# SmartVision.net
KiCad netlist of a schematic drawn in EAGLE
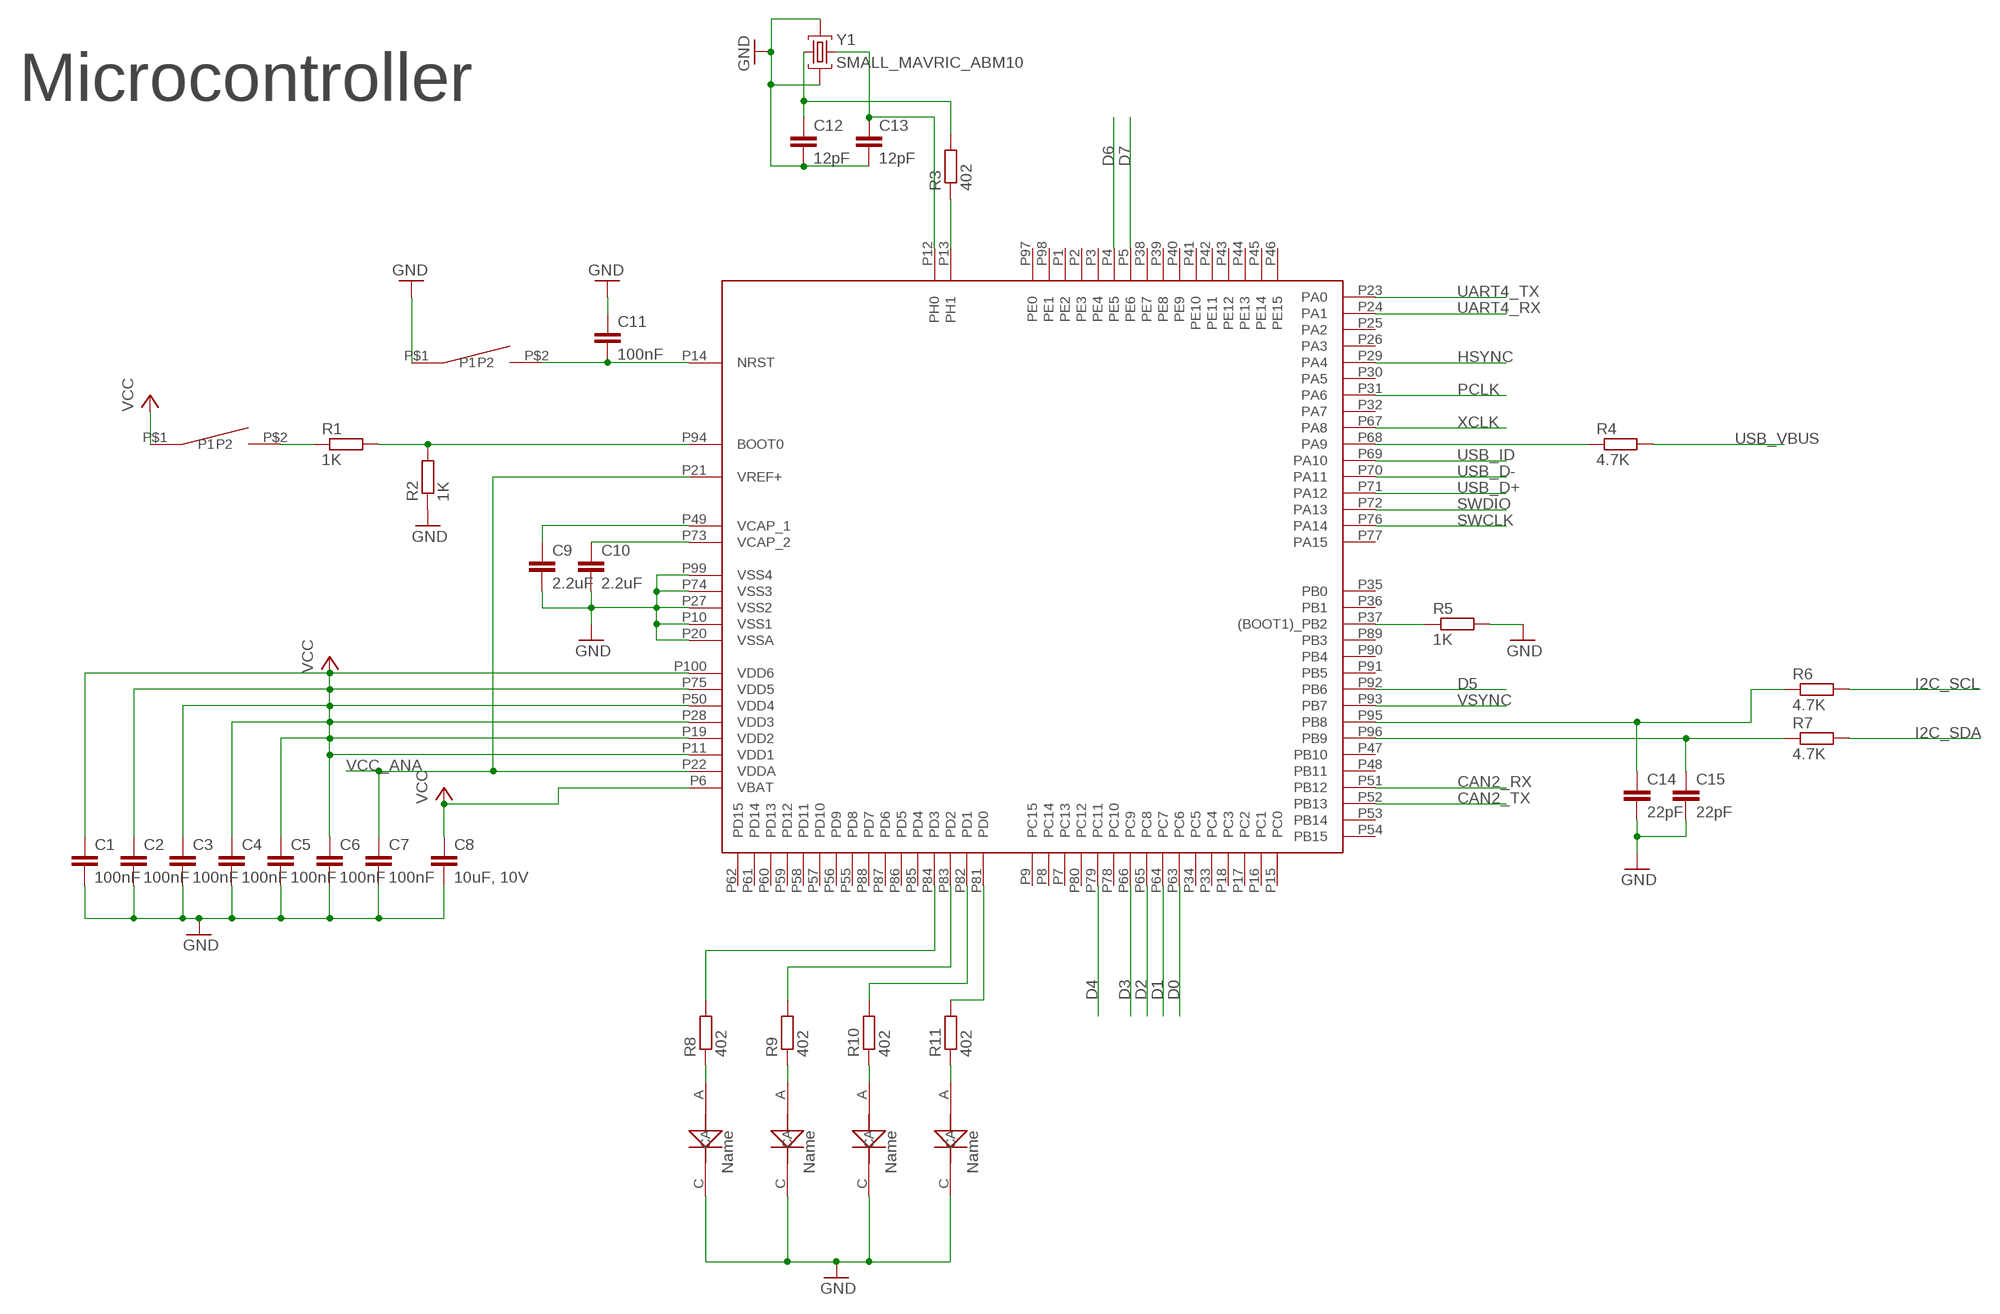
[diagram p0: schematic, sheet 1]
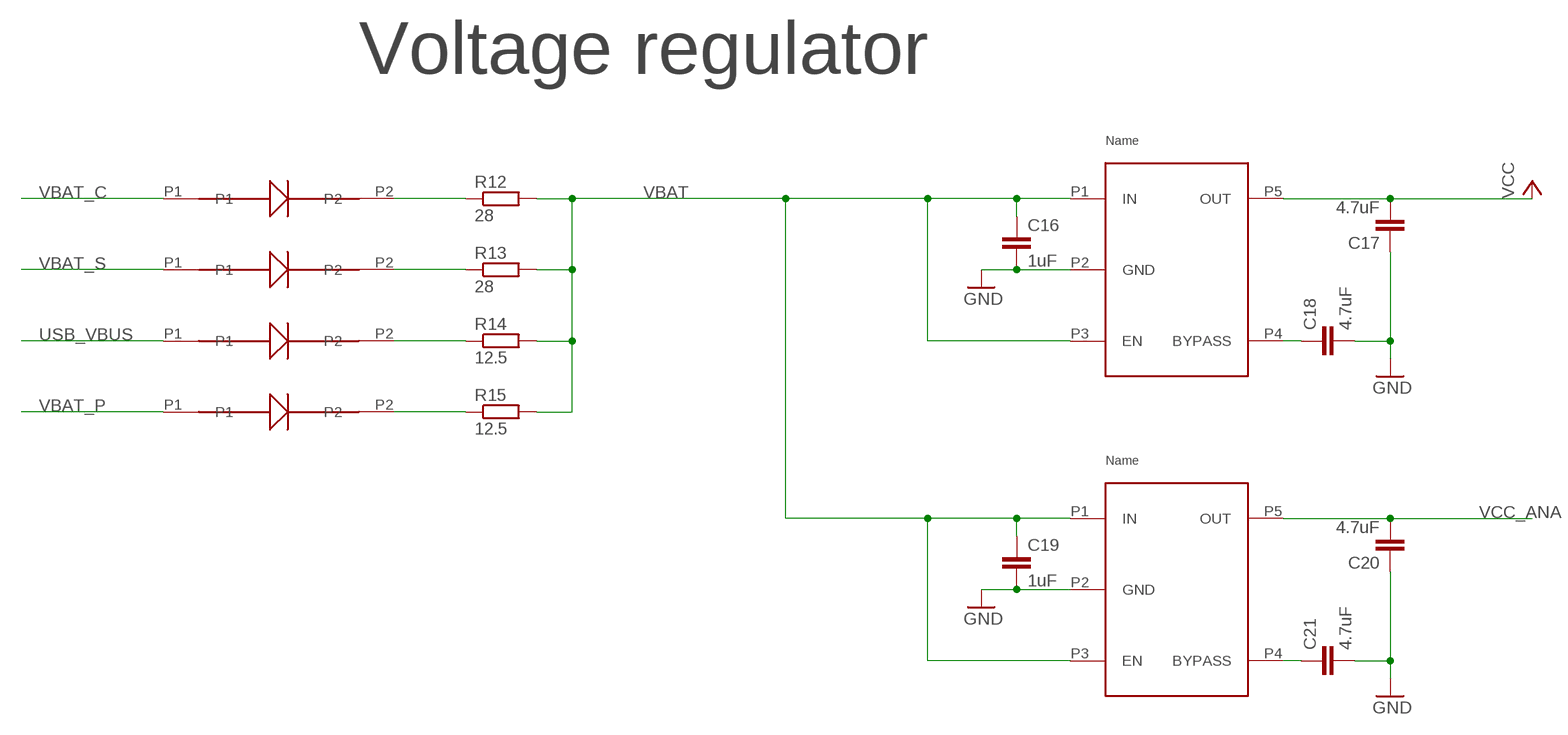
[diagram p1: schematic, sheet 2]
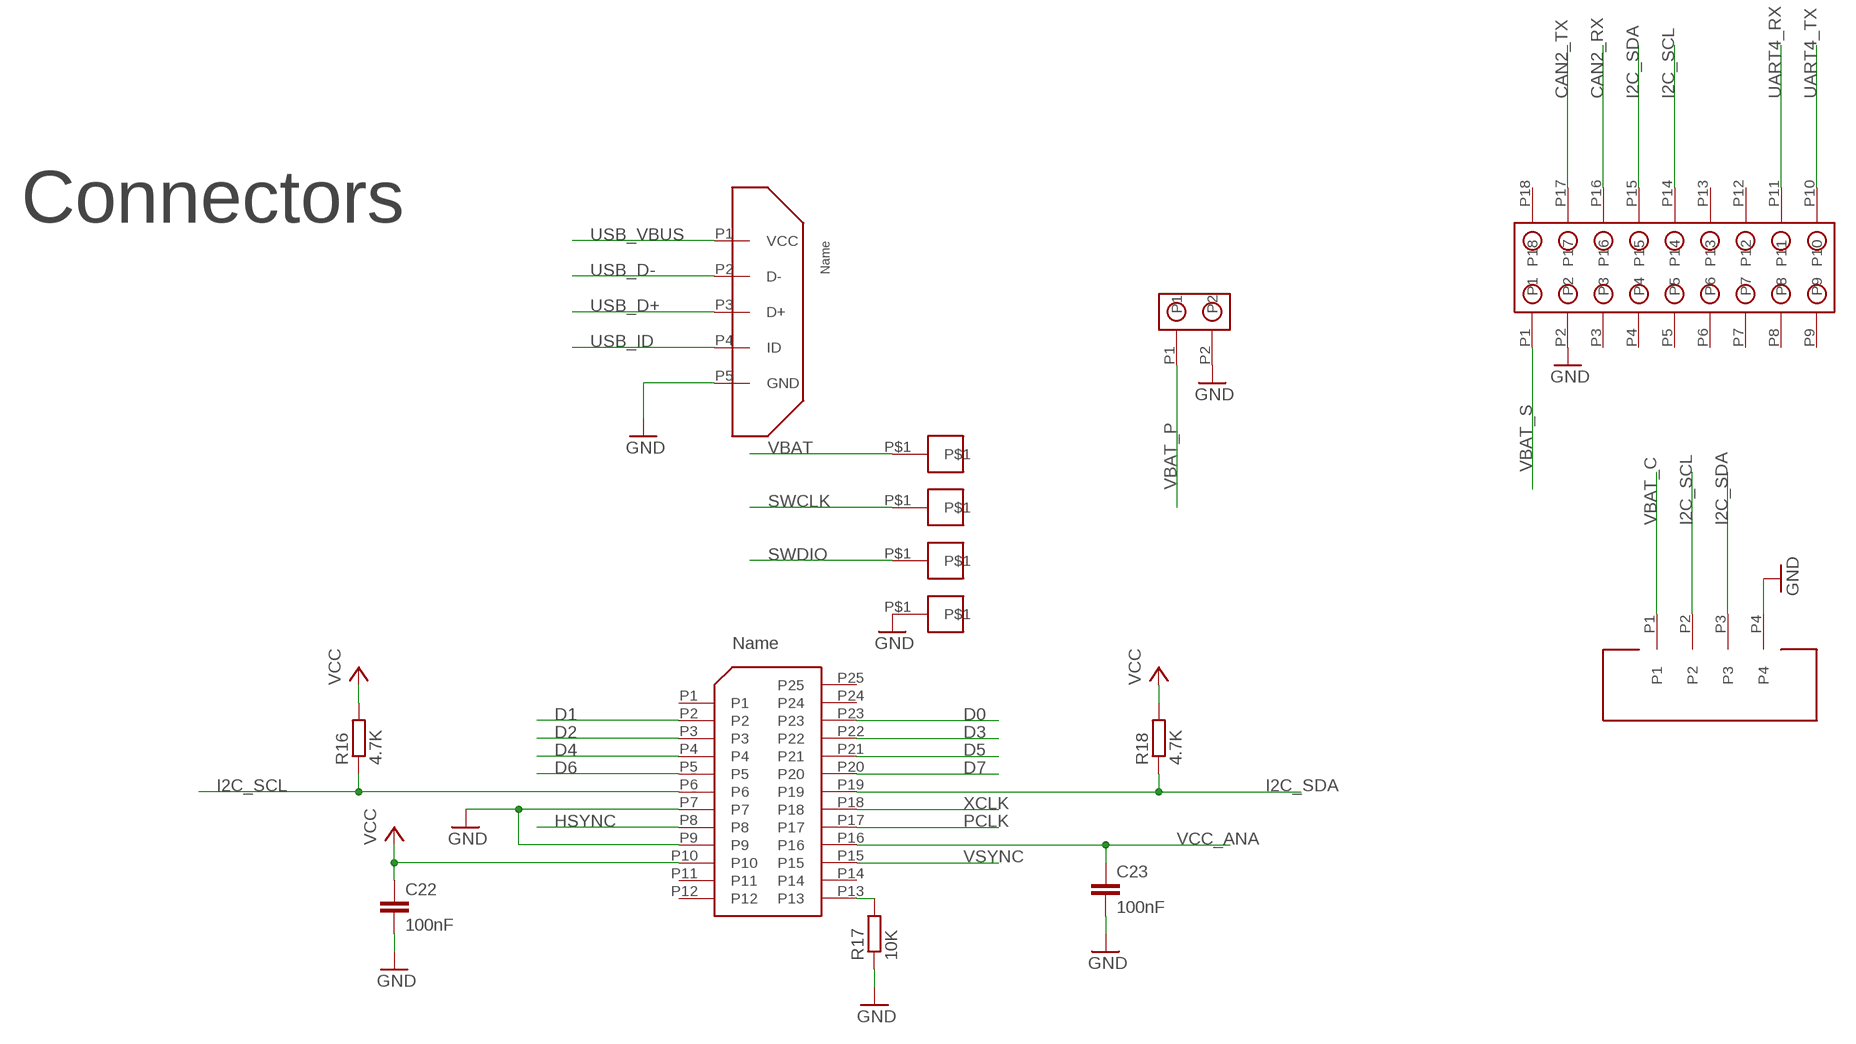
[diagram p2: schematic, sheet 3]
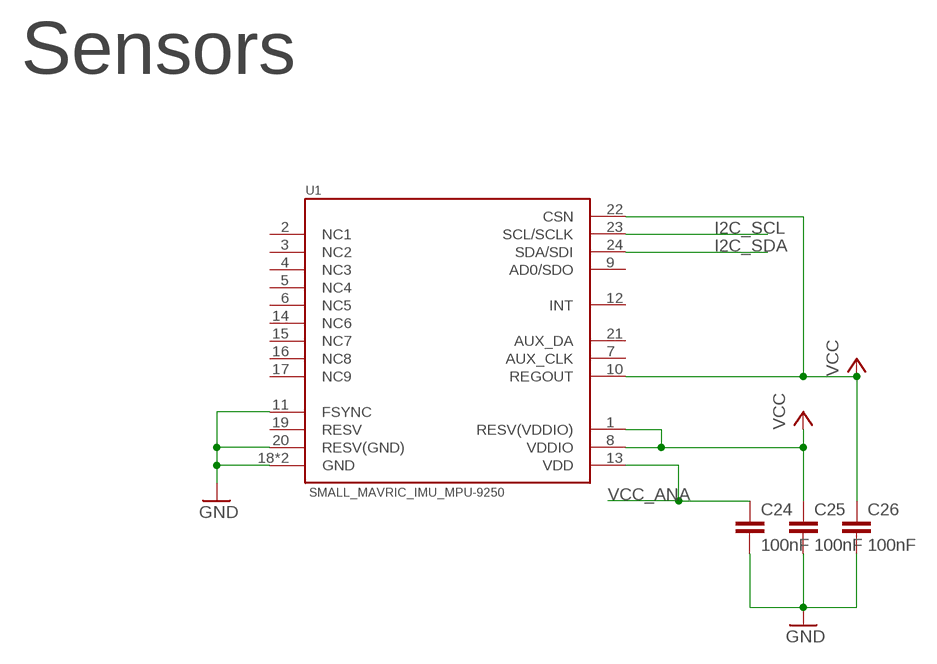
[diagram p3: schematic, sheet 4]

(export (version "E")
  (design (tool "Eeschema 10.0.6"))
  (components
    (comp (ref "C24")
      (value "100nF")
      (footprint "eagle-import:SMALL_MAVRIC_SMALL_MAVRIC_CAPACITOR_C0402")
      (fields (field (name "PLACE_PART") "YES"))
      (libsource (lib "eagle-import") (part "SMALL_MAVRIC_CAPACITOR_C0402"))
    )
    (comp (ref "C25")
      (value "100nF")
      (footprint "eagle-import:SMALL_MAVRIC_SMALL_MAVRIC_CAPACITOR_C0402")
      (fields (field (name "PLACE_PART") "YES"))
      (libsource (lib "eagle-import") (part "SMALL_MAVRIC_CAPACITOR_C0402"))
    )
    (comp (ref "C26")
      (value "100nF")
      (footprint "eagle-import:SMALL_MAVRIC_SMALL_MAVRIC_CAPACITOR_C0402")
      (fields (field (name "PLACE_PART") "YES"))
      (libsource (lib "eagle-import") (part "SMALL_MAVRIC_CAPACITOR_C0402"))
    )
    (comp (ref "U1")
      (value "SMALL_MAVRIC_IMU_MPU-9250")
      (footprint "eagle-import:SMALL_MAVRIC_SMALL_MAVRIC_QFN-24_3.0X3.0MM")
      (fields (field (name "PLACE_PART") "YES"))
      (libsource (lib "eagle-import") (part "SMALL_MAVRIC_IMU_MPU-9250"))
    )
    (comp (ref "C16")
      (value "1uF")
      (footprint "eagle-import:SMALL_MAVRIC_SMALL_MAVRIC_CAPACITOR_C0402")
      (fields (field (name "PLACE_PART") "YES"))
      (libsource (lib "eagle-import") (part "SMALL_MAVRIC_CAPACITOR_C0402"))
    )
    (comp (ref "C17")
      (value "4.7uF")
      (footprint "eagle-import:SMALL_MAVRIC_SMALL_MAVRIC_CAPACITOR_C0603")
      (fields (field (name "PLACE_PART") "YES"))
      (libsource (lib "eagle-import") (part "SMALL_MAVRIC_CAPACITOR_C0603"))
    )
    (comp (ref "C18")
      (value "4.7uF")
      (footprint "eagle-import:SMALL_MAVRIC_SMALL_MAVRIC_CAPACITOR_C0603")
      (fields (field (name "PLACE_PART") "YES"))
      (libsource (lib "eagle-import") (part "SMALL_MAVRIC_CAPACITOR_C0603"))
    )
    (comp (ref "C19")
      (value "1uF")
      (footprint "eagle-import:SMALL_MAVRIC_SMALL_MAVRIC_CAPACITOR_C0402")
      (fields (field (name "PLACE_PART") "YES"))
      (libsource (lib "eagle-import") (part "SMALL_MAVRIC_CAPACITOR_C0402"))
    )
    (comp (ref "C20")
      (value "4.7uF")
      (footprint "eagle-import:SMALL_MAVRIC_SMALL_MAVRIC_CAPACITOR_C0603")
      (fields (field (name "PLACE_PART") "YES"))
      (libsource (lib "eagle-import") (part "SMALL_MAVRIC_CAPACITOR_C0603"))
    )
    (comp (ref "C21")
      (value "4.7uF")
      (footprint "eagle-import:SMALL_MAVRIC_SMALL_MAVRIC_CAPACITOR_C0603")
      (fields (field (name "PLACE_PART") "YES"))
      (libsource (lib "eagle-import") (part "SMALL_MAVRIC_CAPACITOR_C0603"))
    )
    (comp (ref "R12")
      (value "28")
      (footprint "eagle-import:SMALL_MAVRIC_SMALL_MAVRIC_RESISTOR_R0402")
      (fields (field (name "PLACE_PART") "YES"))
      (libsource (lib "eagle-import") (part "SMALL_MAVRIC_RESISTOR_R0402"))
    )
    (comp (ref "R13")
      (value "28")
      (footprint "eagle-import:SMALL_MAVRIC_SMALL_MAVRIC_RESISTOR_R0402")
      (fields (field (name "PLACE_PART") "YES"))
      (libsource (lib "eagle-import") (part "SMALL_MAVRIC_RESISTOR_R0402"))
    )
    (comp (ref "R14")
      (value "12.5")
      (footprint "eagle-import:SMALL_MAVRIC_SMALL_MAVRIC_RESISTOR_R0402")
      (fields (field (name "PLACE_PART") "YES"))
      (libsource (lib "eagle-import") (part "SMALL_MAVRIC_RESISTOR_R0402"))
    )
    (comp (ref "R15")
      (value "12.5")
      (footprint "eagle-import:SMALL_MAVRIC_SMALL_MAVRIC_RESISTOR_R0402")
      (fields (field (name "PLACE_PART") "YES"))
      (libsource (lib "eagle-import") (part "SMALL_MAVRIC_RESISTOR_R0402"))
    )
    (comp (ref "U$2")
      (value "VOLTAGE_REGULATOR_3V")
      (footprint "eagle-import:VOLTAGE_REGULATOR_3V")
      (libsource (lib "eagle-import") (part "VOLTAGE_REGULATOR_3V"))
    )
    (comp (ref "U$7")
      (value "VOLTAGE_REGULATOR_3V")
      (footprint "eagle-import:VOLTAGE_REGULATOR_3V")
      (libsource (lib "eagle-import") (part "VOLTAGE_REGULATOR_3V"))
    )
    (comp (ref "U$54")
      (value "DIODE_SCHOTTKY")
      (footprint "eagle-import:DIODE_SCHOTTKY")
      (libsource (lib "eagle-import") (part "DIODE_SCHOTTKY"))
    )
    (comp (ref "U$55")
      (value "DIODE_SCHOTTKY")
      (footprint "eagle-import:DIODE_SCHOTTKY")
      (libsource (lib "eagle-import") (part "DIODE_SCHOTTKY"))
    )
    (comp (ref "U$57")
      (value "DIODE_SCHOTTKY")
      (footprint "eagle-import:DIODE_SCHOTTKY")
      (libsource (lib "eagle-import") (part "DIODE_SCHOTTKY"))
    )
    (comp (ref "U$61")
      (value "DIODE_SCHOTTKY")
      (footprint "eagle-import:DIODE_SCHOTTKY")
      (libsource (lib "eagle-import") (part "DIODE_SCHOTTKY"))
    )
    (comp (ref "C1")
      (value "100nF")
      (footprint "eagle-import:SMALL_MAVRIC_SMALL_MAVRIC_CAPACITOR_C0402")
      (fields (field (name "PLACE_PART") "YES"))
      (libsource (lib "eagle-import") (part "SMALL_MAVRIC_CAPACITOR_C0402"))
    )
    (comp (ref "C2")
      (value "100nF")
      (footprint "eagle-import:SMALL_MAVRIC_SMALL_MAVRIC_CAPACITOR_C0402")
      (fields (field (name "PLACE_PART") "YES"))
      (libsource (lib "eagle-import") (part "SMALL_MAVRIC_CAPACITOR_C0402"))
    )
    (comp (ref "C3")
      (value "100nF")
      (footprint "eagle-import:SMALL_MAVRIC_SMALL_MAVRIC_CAPACITOR_C0402")
      (fields (field (name "PLACE_PART") "YES"))
      (libsource (lib "eagle-import") (part "SMALL_MAVRIC_CAPACITOR_C0402"))
    )
    (comp (ref "C4")
      (value "100nF")
      (footprint "eagle-import:SMALL_MAVRIC_SMALL_MAVRIC_CAPACITOR_C0402")
      (fields (field (name "PLACE_PART") "YES"))
      (libsource (lib "eagle-import") (part "SMALL_MAVRIC_CAPACITOR_C0402"))
    )
    (comp (ref "C5")
      (value "100nF")
      (footprint "eagle-import:SMALL_MAVRIC_SMALL_MAVRIC_CAPACITOR_C0402")
      (fields (field (name "PLACE_PART") "YES"))
      (libsource (lib "eagle-import") (part "SMALL_MAVRIC_CAPACITOR_C0402"))
    )
    (comp (ref "C6")
      (value "100nF")
      (footprint "eagle-import:SMALL_MAVRIC_SMALL_MAVRIC_CAPACITOR_C0402")
      (fields (field (name "PLACE_PART") "YES"))
      (libsource (lib "eagle-import") (part "SMALL_MAVRIC_CAPACITOR_C0402"))
    )
    (comp (ref "C7")
      (value "100nF")
      (footprint "eagle-import:SMALL_MAVRIC_SMALL_MAVRIC_CAPACITOR_C0402")
      (fields (field (name "PLACE_PART") "YES"))
      (libsource (lib "eagle-import") (part "SMALL_MAVRIC_CAPACITOR_C0402"))
    )
    (comp (ref "C8")
      (value "10uF, 10V")
      (footprint "eagle-import:SMALL_MAVRIC_SMALL_MAVRIC_CAPACITOR_C0603")
      (fields (field (name "PLACE_PART") "YES"))
      (libsource (lib "eagle-import") (part "SMALL_MAVRIC_CAPACITOR_C0603"))
    )
    (comp (ref "C9")
      (value "2.2uF")
      (footprint "eagle-import:SMALL_MAVRIC_SMALL_MAVRIC_CAPACITOR_C0402")
      (fields (field (name "PLACE_PART") "YES"))
      (libsource (lib "eagle-import") (part "SMALL_MAVRIC_CAPACITOR_C0402"))
    )
    (comp (ref "C10")
      (value "2.2uF")
      (footprint "eagle-import:SMALL_MAVRIC_SMALL_MAVRIC_CAPACITOR_C0402")
      (fields (field (name "PLACE_PART") "YES"))
      (libsource (lib "eagle-import") (part "SMALL_MAVRIC_CAPACITOR_C0402"))
    )
    (comp (ref "C11")
      (value "100nF")
      (footprint "eagle-import:SMALL_MAVRIC_SMALL_MAVRIC_CAPACITOR_C0402")
      (fields (field (name "PLACE_PART") "YES"))
      (libsource (lib "eagle-import") (part "SMALL_MAVRIC_CAPACITOR_C0402"))
    )
    (comp (ref "C12")
      (value "12pF")
      (footprint "eagle-import:SMALL_MAVRIC_SMALL_MAVRIC_CAPACITOR_C0402")
      (fields (field (name "PLACE_PART") "YES"))
      (libsource (lib "eagle-import") (part "SMALL_MAVRIC_CAPACITOR_C0402"))
    )
    (comp (ref "C13")
      (value "12pF")
      (footprint "eagle-import:SMALL_MAVRIC_SMALL_MAVRIC_CAPACITOR_C0402")
      (fields (field (name "PLACE_PART") "YES"))
      (libsource (lib "eagle-import") (part "SMALL_MAVRIC_CAPACITOR_C0402"))
    )
    (comp (ref "C14")
      (value "22pF")
      (footprint "eagle-import:SMALL_MAVRIC_SMALL_MAVRIC_CAPACITOR_C0402")
      (fields (field (name "PLACE_PART") "YES"))
      (libsource (lib "eagle-import") (part "SMALL_MAVRIC_CAPACITOR_C0402"))
    )
    (comp (ref "C15")
      (value "22pF")
      (footprint "eagle-import:SMALL_MAVRIC_SMALL_MAVRIC_CAPACITOR_C0402")
      (fields (field (name "PLACE_PART") "YES"))
      (libsource (lib "eagle-import") (part "SMALL_MAVRIC_CAPACITOR_C0402"))
    )
    (comp (ref "R1")
      (value "1K")
      (footprint "eagle-import:SMALL_MAVRIC_SMALL_MAVRIC_RESISTOR_R0402")
      (fields (field (name "PLACE_PART") "YES"))
      (libsource (lib "eagle-import") (part "SMALL_MAVRIC_RESISTOR_R0402"))
    )
    (comp (ref "R2")
      (value "1K")
      (footprint "eagle-import:SMALL_MAVRIC_SMALL_MAVRIC_RESISTOR_R0402")
      (fields (field (name "PLACE_PART") "YES"))
      (libsource (lib "eagle-import") (part "SMALL_MAVRIC_RESISTOR_R0402"))
    )
    (comp (ref "R3")
      (value "402")
      (footprint "eagle-import:SMALL_MAVRIC_SMALL_MAVRIC_RESISTOR_R0402")
      (fields (field (name "PLACE_PART") "YES"))
      (libsource (lib "eagle-import") (part "SMALL_MAVRIC_RESISTOR_R0402"))
    )
    (comp (ref "R4")
      (value "4.7K")
      (footprint "eagle-import:SMALL_MAVRIC_SMALL_MAVRIC_RESISTOR_R0402")
      (fields (field (name "PLACE_PART") "YES"))
      (libsource (lib "eagle-import") (part "SMALL_MAVRIC_RESISTOR_R0402"))
    )
    (comp (ref "R5")
      (value "1K")
      (footprint "eagle-import:SMALL_MAVRIC_SMALL_MAVRIC_RESISTOR_R0402")
      (fields (field (name "PLACE_PART") "YES"))
      (libsource (lib "eagle-import") (part "SMALL_MAVRIC_RESISTOR_R0402"))
    )
    (comp (ref "R6")
      (value "4.7K")
      (footprint "eagle-import:SMALL_MAVRIC_SMALL_MAVRIC_RESISTOR_R0402")
      (fields (field (name "PLACE_PART") "YES"))
      (libsource (lib "eagle-import") (part "SMALL_MAVRIC_RESISTOR_R0402"))
    )
    (comp (ref "R7")
      (value "4.7K")
      (footprint "eagle-import:SMALL_MAVRIC_SMALL_MAVRIC_RESISTOR_R0402")
      (fields (field (name "PLACE_PART") "YES"))
      (libsource (lib "eagle-import") (part "SMALL_MAVRIC_RESISTOR_R0402"))
    )
    (comp (ref "R8")
      (value "402")
      (footprint "eagle-import:SMALL_MAVRIC_SMALL_MAVRIC_RESISTOR_R0402")
      (fields (field (name "PLACE_PART") "YES"))
      (libsource (lib "eagle-import") (part "SMALL_MAVRIC_RESISTOR_R0402"))
    )
    (comp (ref "R9")
      (value "402")
      (footprint "eagle-import:SMALL_MAVRIC_SMALL_MAVRIC_RESISTOR_R0402")
      (fields (field (name "PLACE_PART") "YES"))
      (libsource (lib "eagle-import") (part "SMALL_MAVRIC_RESISTOR_R0402"))
    )
    (comp (ref "R10")
      (value "402")
      (footprint "eagle-import:SMALL_MAVRIC_SMALL_MAVRIC_RESISTOR_R0402")
      (fields (field (name "PLACE_PART") "YES"))
      (libsource (lib "eagle-import") (part "SMALL_MAVRIC_RESISTOR_R0402"))
    )
    (comp (ref "R11")
      (value "402")
      (footprint "eagle-import:SMALL_MAVRIC_SMALL_MAVRIC_RESISTOR_R0402")
      (fields (field (name "PLACE_PART") "YES"))
      (libsource (lib "eagle-import") (part "SMALL_MAVRIC_RESISTOR_R0402"))
    )
    (comp (ref "U$1")
      (value "STM32F407VGT6-100")
      (footprint "eagle-import:STM32F407VGT6-100")
      (libsource (lib "eagle-import") (part "STM32F407VGT6-100"))
    )
    (comp (ref "U$29")
      (value "SWITCH_OFF_(ON)")
      (footprint "eagle-import:SWITCH_OFF_(ON)")
      (libsource (lib "eagle-import") (part "SWITCH_OFF_(ON)"))
    )
    (comp (ref "U$31")
      (value "SWITCH_OFF_(ON)")
      (footprint "eagle-import:SWITCH_OFF_(ON)")
      (libsource (lib "eagle-import") (part "SWITCH_OFF_(ON)"))
    )
    (comp (ref "U$40")
      (value "LED")
      (footprint "eagle-import:LED")
      (libsource (lib "eagle-import") (part "LED"))
    )
    (comp (ref "U$41")
      (value "LED")
      (footprint "eagle-import:LED")
      (libsource (lib "eagle-import") (part "LED"))
    )
    (comp (ref "U$42")
      (value "LED")
      (footprint "eagle-import:LED")
      (libsource (lib "eagle-import") (part "LED"))
    )
    (comp (ref "U$43")
      (value "LED")
      (footprint "eagle-import:LED")
      (libsource (lib "eagle-import") (part "LED"))
    )
    (comp (ref "Y1")
      (value "SMALL_MAVRIC_ABM10")
      (footprint "eagle-import:SMALL_MAVRIC_OSCILLATOR_ABM10")
      (libsource (lib "eagle-import") (part "SMALL_MAVRIC_ABM10"))
    )
    (comp (ref "C22")
      (value "100nF")
      (footprint "eagle-import:SMALL_MAVRIC_SMALL_MAVRIC_CAPACITOR_C0402")
      (fields (field (name "PLACE_PART") "YES"))
      (libsource (lib "eagle-import") (part "SMALL_MAVRIC_CAPACITOR_C0402"))
    )
    (comp (ref "C23")
      (value "100nF")
      (footprint "eagle-import:SMALL_MAVRIC_SMALL_MAVRIC_CAPACITOR_C0402")
      (fields (field (name "PLACE_PART") "YES"))
      (libsource (lib "eagle-import") (part "SMALL_MAVRIC_CAPACITOR_C0402"))
    )
    (comp (ref "R16")
      (value "4.7K")
      (footprint "eagle-import:SMALL_MAVRIC_SMALL_MAVRIC_RESISTOR_R0402")
      (fields (field (name "PLACE_PART") "YES"))
      (libsource (lib "eagle-import") (part "SMALL_MAVRIC_RESISTOR_R0402"))
    )
    (comp (ref "R17")
      (value "10K")
      (footprint "eagle-import:SMALL_MAVRIC_SMALL_MAVRIC_RESISTOR_R0402")
      (fields (field (name "PLACE_PART") "YES"))
      (libsource (lib "eagle-import") (part "SMALL_MAVRIC_RESISTOR_R0402"))
    )
    (comp (ref "R18")
      (value "4.7K")
      (footprint "eagle-import:SMALL_MAVRIC_SMALL_MAVRIC_RESISTOR_R0402")
      (fields (field (name "PLACE_PART") "YES"))
      (libsource (lib "eagle-import") (part "SMALL_MAVRIC_RESISTOR_R0402"))
    )
    (comp (ref "U$3")
      (value "PAD_FLASH")
      (footprint "eagle-import:PAD_FLASH")
      (libsource (lib "eagle-import") (part "PAD_FLASH"))
    )
    (comp (ref "U$4")
      (value "MICRO_USB_PLUG")
      (footprint "eagle-import:MICRO_USB_PLUG")
      (libsource (lib "eagle-import") (part "MICRO_USB_PLUG"))
    )
    (comp (ref "U$5")
      (value "PAD_FLASH")
      (footprint "eagle-import:PAD_FLASH")
      (libsource (lib "eagle-import") (part "PAD_FLASH"))
    )
    (comp (ref "U$11")
      (value "CON_CAMERA_FPC_25P_0.3MM")
      (footprint "eagle-import:CON_CAMERA_FPC_25P_0.3MM")
      (libsource (lib "eagle-import") (part "CON_CAMERA_FPC_25P_0.3MM"))
    )
    (comp (ref "U$52")
      (value "CON_2.54MM_18PINS_STACKABLE")
      (footprint "eagle-import:CON_2.54MM_18PINS_STACKABLE")
      (libsource (lib "eagle-import") (part "CON_2.54MM_18PINS_STACKABLE"))
    )
    (comp (ref "U$53")
      (value "CON_1.25MM_4PINS")
      (footprint "eagle-import:CON_1.25MM_4PINS")
      (libsource (lib "eagle-import") (part "CON_1.25MM_4PINS"))
    )
    (comp (ref "U$59")
      (value "CON_2.54MM_2PINS")
      (footprint "eagle-import:CON_2.54MM_2PINS")
      (libsource (lib "eagle-import") (part "CON_2.54MM_2PINS"))
    )
    (comp (ref "U$63")
      (value "PAD_FLASH")
      (footprint "eagle-import:PAD_FLASH")
      (libsource (lib "eagle-import") (part "PAD_FLASH"))
    )
    (comp (ref "U$64")
      (value "PAD_FLASH")
      (footprint "eagle-import:PAD_FLASH")
      (libsource (lib "eagle-import") (part "PAD_FLASH"))
    )
  )
  (nets
    (net (code "1") (name "CAN2_RX") (class "Default")
      (node (ref "U$1") (pin "P51") (pinfunction "PB12_P51") (pintype "bidirectional"))
      (node (ref "U$52") (pin "P16") (pinfunction "P16_P16") (pintype "bidirectional"))
    )
    (net (code "2") (name "CAN2_TX") (class "Default")
      (node (ref "U$1") (pin "P52") (pinfunction "PB13_P52") (pintype "bidirectional"))
      (node (ref "U$52") (pin "P17") (pinfunction "P17_P17") (pintype "bidirectional"))
    )
    (net (code "3") (name "D0") (class "Default")
      (node (ref "U$1") (pin "P63") (pinfunction "PC6_P63") (pintype "bidirectional"))
      (node (ref "U$11") (pin "P23") (pinfunction "P23_P23") (pintype "bidirectional"))
    )
    (net (code "4") (name "D1") (class "Default")
      (node (ref "U$1") (pin "P64") (pinfunction "PC7_P64") (pintype "bidirectional"))
      (node (ref "U$11") (pin "P2") (pinfunction "P2_P2") (pintype "bidirectional"))
    )
    (net (code "5") (name "D2") (class "Default")
      (node (ref "U$1") (pin "P65") (pinfunction "PC8_P65") (pintype "bidirectional"))
      (node (ref "U$11") (pin "P3") (pinfunction "P3_P3") (pintype "bidirectional"))
    )
    (net (code "6") (name "D3") (class "Default")
      (node (ref "U$1") (pin "P66") (pinfunction "PC9_P66") (pintype "bidirectional"))
      (node (ref "U$11") (pin "P22") (pinfunction "P22_P22") (pintype "bidirectional"))
    )
    (net (code "7") (name "D4") (class "Default")
      (node (ref "U$1") (pin "P79") (pinfunction "PC11_P79") (pintype "bidirectional"))
      (node (ref "U$11") (pin "P4") (pinfunction "P4_P4") (pintype "bidirectional"))
    )
    (net (code "8") (name "D5") (class "Default")
      (node (ref "U$1") (pin "P92") (pinfunction "PB6_P92") (pintype "bidirectional"))
      (node (ref "U$11") (pin "P21") (pinfunction "P21_P21") (pintype "bidirectional"))
    )
    (net (code "9") (name "D6") (class "Default")
      (node (ref "U$1") (pin "P4") (pinfunction "PE5_P4") (pintype "bidirectional"))
      (node (ref "U$11") (pin "P5") (pinfunction "P5_P5") (pintype "bidirectional"))
    )
    (net (code "10") (name "D7") (class "Default")
      (node (ref "U$1") (pin "P5") (pinfunction "PE6_P5") (pintype "bidirectional"))
      (node (ref "U$11") (pin "P20") (pinfunction "P20_P20") (pintype "bidirectional"))
    )
    (net (code "11") (name "GND") (class "Default")
      (node (ref "C1") (pin "2") (pinfunction "2_2") (pintype "passive"))
      (node (ref "C10") (pin "2") (pinfunction "2_2") (pintype "passive"))
      (node (ref "C11") (pin "1") (pinfunction "1_1") (pintype "passive"))
      (node (ref "C12") (pin "2") (pinfunction "2_2") (pintype "passive"))
      (node (ref "C13") (pin "2") (pinfunction "2_2") (pintype "passive"))
      (node (ref "C14") (pin "2") (pinfunction "2_2") (pintype "passive"))
      (node (ref "C15") (pin "2") (pinfunction "2_2") (pintype "passive"))
      (node (ref "C16") (pin "2") (pinfunction "2_2") (pintype "passive"))
      (node (ref "C17") (pin "1") (pinfunction "1_1") (pintype "passive"))
      (node (ref "C18") (pin "2") (pinfunction "2_2") (pintype "passive"))
      (node (ref "C19") (pin "2") (pinfunction "2_2") (pintype "passive"))
      (node (ref "C2") (pin "2") (pinfunction "2_2") (pintype "passive"))
      (node (ref "C20") (pin "1") (pinfunction "1_1") (pintype "passive"))
      (node (ref "C21") (pin "2") (pinfunction "2_2") (pintype "passive"))
      (node (ref "C22") (pin "2") (pinfunction "2_2") (pintype "passive"))
      (node (ref "C23") (pin "2") (pinfunction "2_2") (pintype "passive"))
      (node (ref "C24") (pin "2") (pinfunction "2_2") (pintype "passive"))
      (node (ref "C25") (pin "2") (pinfunction "2_2") (pintype "passive"))
      (node (ref "C26") (pin "2") (pinfunction "2_2") (pintype "passive"))
      (node (ref "C3") (pin "2") (pinfunction "2_2") (pintype "passive"))
      (node (ref "C4") (pin "2") (pinfunction "2_2") (pintype "passive"))
      (node (ref "C5") (pin "2") (pinfunction "2_2") (pintype "passive"))
      (node (ref "C6") (pin "2") (pinfunction "2_2") (pintype "passive"))
      (node (ref "C7") (pin "2") (pinfunction "2_2") (pintype "passive"))
      (node (ref "C8") (pin "2") (pinfunction "2_2") (pintype "passive"))
      (node (ref "C9") (pin "2") (pinfunction "2_2") (pintype "passive"))
      (node (ref "R17") (pin "1") (pinfunction "1_1") (pintype "passive"))
      (node (ref "R2") (pin "1") (pinfunction "1_1") (pintype "passive"))
      (node (ref "R5") (pin "2") (pinfunction "2_2") (pintype "passive"))
      (node (ref "U$1") (pin "P10") (pinfunction "VSS1_P10") (pintype "bidirectional"))
      (node (ref "U$1") (pin "P20") (pinfunction "VSSA_P20") (pintype "bidirectional"))
      (node (ref "U$1") (pin "P27") (pinfunction "VSS2_P27") (pintype "bidirectional"))
      (node (ref "U$1") (pin "P74") (pinfunction "VSS3_P74") (pintype "bidirectional"))
      (node (ref "U$1") (pin "P99") (pinfunction "VSS4_P99") (pintype "bidirectional"))
      (node (ref "U$11") (pin "P7") (pinfunction "P7_P7") (pintype "bidirectional"))
      (node (ref "U$11") (pin "P9") (pinfunction "P9_P9") (pintype "bidirectional"))
      (node (ref "U$2") (pin "P2") (pinfunction "GND_P2") (pintype "bidirectional"))
      (node (ref "U$29") (pin "P$1") (pinfunction "P1_P$1") (pintype "bidirectional"))
      (node (ref "U$3") (pin "P$1") (pinfunction "P$1_P$1") (pintype "bidirectional"))
      (node (ref "U$4") (pin "P5") (pinfunction "GND_P5") (pintype "bidirectional"))
      (node (ref "U$40") (pin "C") (pinfunction "C_C") (pintype "bidirectional"))
      (node (ref "U$41") (pin "C") (pinfunction "C_C") (pintype "bidirectional"))
      (node (ref "U$42") (pin "C") (pinfunction "C_C") (pintype "bidirectional"))
      (node (ref "U$43") (pin "C") (pinfunction "C_C") (pintype "bidirectional"))
      (node (ref "U$52") (pin "P2") (pinfunction "P2_P2") (pintype "bidirectional"))
      (node (ref "U$53") (pin "P4") (pinfunction "P4_P4") (pintype "bidirectional"))
      (node (ref "U$59") (pin "P2") (pinfunction "P2_P2") (pintype "bidirectional"))
      (node (ref "U$7") (pin "P2") (pinfunction "GND_P2") (pintype "bidirectional"))
      (node (ref "U1") (pin "11") (pinfunction "FSYNC_11") (pintype "bidirectional"))
      (node (ref "U1") (pin "18") (pinfunction "GND_18") (pintype "power_in"))
      (node (ref "U1") (pin "20") (pinfunction "RESV(GND)_20") (pintype "passive"))
      (node (ref "U1") (pin "CENTRAL_PAD") (pinfunction "GND_CENTRAL_PAD") (pintype "power_in"))
      (node (ref "Y1") (pin "2") (pinfunction "2_2") (pintype "passive"))
      (node (ref "Y1") (pin "4") (pinfunction "4_4") (pintype "passive"))
    )
    (net (code "12") (name "HSYNC") (class "Default")
      (node (ref "U$1") (pin "P29") (pinfunction "PA4_P29") (pintype "bidirectional"))
      (node (ref "U$11") (pin "P8") (pinfunction "P8_P8") (pintype "bidirectional"))
    )
    (net (code "13") (name "I2C_SCL") (class "Default")
      (node (ref "R16") (pin "1") (pinfunction "1_1") (pintype "passive"))
      (node (ref "R6") (pin "2") (pinfunction "2_2") (pintype "passive"))
      (node (ref "U$11") (pin "P6") (pinfunction "P6_P6") (pintype "bidirectional"))
      (node (ref "U$52") (pin "P14") (pinfunction "P14_P14") (pintype "bidirectional"))
      (node (ref "U$53") (pin "P2") (pinfunction "P2_P2") (pintype "bidirectional"))
      (node (ref "U1") (pin "23") (pinfunction "SCL/SCLK_23") (pintype "input"))
    )
    (net (code "14") (name "I2C_SDA") (class "Default")
      (node (ref "R18") (pin "1") (pinfunction "1_1") (pintype "passive"))
      (node (ref "R7") (pin "2") (pinfunction "2_2") (pintype "passive"))
      (node (ref "U$11") (pin "P19") (pinfunction "P19_P19") (pintype "bidirectional"))
      (node (ref "U$52") (pin "P15") (pinfunction "P15_P15") (pintype "bidirectional"))
      (node (ref "U$53") (pin "P3") (pinfunction "P3_P3") (pintype "bidirectional"))
      (node (ref "U1") (pin "24") (pinfunction "SDA/SDI_24") (pintype "input"))
    )
    (net (code "15") (name "Net-(C12-Pad1)") (class "Default")
      (node (ref "C12") (pin "1") (pinfunction "1_1") (pintype "passive"))
      (node (ref "R3") (pin "2") (pinfunction "2_2") (pintype "passive"))
      (node (ref "Y1") (pin "1") (pinfunction "1_1") (pintype "passive"))
    )
    (net (code "16") (name "Net-(R8-Pad1)") (class "Default")
      (node (ref "R8") (pin "1") (pinfunction "1_1") (pintype "passive"))
      (node (ref "U$40") (pin "A") (pinfunction "A_A") (pintype "bidirectional"))
    )
    (net (code "17") (name "Net-(R9-Pad1)") (class "Default")
      (node (ref "R9") (pin "1") (pinfunction "1_1") (pintype "passive"))
      (node (ref "U$41") (pin "A") (pinfunction "A_A") (pintype "bidirectional"))
    )
    (net (code "18") (name "Net-(R10-Pad1)") (class "Default")
      (node (ref "R10") (pin "1") (pinfunction "1_1") (pintype "passive"))
      (node (ref "U$42") (pin "A") (pinfunction "A_A") (pintype "bidirectional"))
    )
    (net (code "19") (name "Net-(R11-Pad1)") (class "Default")
      (node (ref "R11") (pin "1") (pinfunction "1_1") (pintype "passive"))
      (node (ref "U$43") (pin "A") (pinfunction "A_A") (pintype "bidirectional"))
    )
    (net (code "20") (name "Net-(R12-Pad1)") (class "Default")
      (node (ref "R12") (pin "1") (pinfunction "1_1") (pintype "passive"))
      (node (ref "U$55") (pin "P2") (pinfunction "P2_P2") (pintype "bidirectional"))
    )
    (net (code "21") (name "Net-(R13-Pad1)") (class "Default")
      (node (ref "R13") (pin "1") (pinfunction "1_1") (pintype "passive"))
      (node (ref "U$61") (pin "P2") (pinfunction "P2_P2") (pintype "bidirectional"))
    )
    (net (code "22") (name "Net-(R14-Pad1)") (class "Default")
      (node (ref "R14") (pin "1") (pinfunction "1_1") (pintype "passive"))
      (node (ref "U$57") (pin "P2") (pinfunction "P2_P2") (pintype "bidirectional"))
    )
    (net (code "23") (name "Net-(R15-Pad1)") (class "Default")
      (node (ref "R15") (pin "1") (pinfunction "1_1") (pintype "passive"))
      (node (ref "U$54") (pin "P2") (pinfunction "P2_P2") (pintype "bidirectional"))
    )
    (net (code "24") (name "Net-(R17-Pad2)") (class "Default")
      (node (ref "R17") (pin "2") (pinfunction "2_2") (pintype "passive"))
      (node (ref "U$11") (pin "P13") (pinfunction "P13_P13") (pintype "bidirectional"))
    )
    (net (code "25") (name "Net-(U$1-(BOOT1)_PB2)") (class "Default")
      (node (ref "R5") (pin "1") (pinfunction "1_1") (pintype "passive"))
      (node (ref "U$1") (pin "P37") (pinfunction "(BOOT1)_PB2_P37") (pintype "bidirectional"))
    )
    (net (code "26") (name "Net-(U$1-BOOT0)") (class "Default")
      (node (ref "R1") (pin "2") (pinfunction "2_2") (pintype "passive"))
      (node (ref "R2") (pin "2") (pinfunction "2_2") (pintype "passive"))
      (node (ref "U$1") (pin "P94") (pinfunction "BOOT0_P94") (pintype "bidirectional"))
    )
    (net (code "27") (name "Net-(U$1-NRST)") (class "Default")
      (node (ref "C11") (pin "2") (pinfunction "2_2") (pintype "passive"))
      (node (ref "U$1") (pin "P14") (pinfunction "NRST_P14") (pintype "bidirectional"))
      (node (ref "U$29") (pin "P$2") (pinfunction "P2_P$2") (pintype "bidirectional"))
    )
    (net (code "28") (name "Net-(U$1-PA9)") (class "Default")
      (node (ref "R4") (pin "1") (pinfunction "1_1") (pintype "passive"))
      (node (ref "U$1") (pin "P68") (pinfunction "PA9_P68") (pintype "bidirectional"))
    )
    (net (code "29") (name "Net-(U$1-PB8)") (class "Default")
      (node (ref "C14") (pin "1") (pinfunction "1_1") (pintype "passive"))
      (node (ref "R6") (pin "1") (pinfunction "1_1") (pintype "passive"))
      (node (ref "U$1") (pin "P95") (pinfunction "PB8_P95") (pintype "bidirectional"))
    )
    (net (code "30") (name "Net-(U$1-PB9)") (class "Default")
      (node (ref "C15") (pin "1") (pinfunction "1_1") (pintype "passive"))
      (node (ref "R7") (pin "1") (pinfunction "1_1") (pintype "passive"))
      (node (ref "U$1") (pin "P96") (pinfunction "PB9_P96") (pintype "bidirectional"))
    )
    (net (code "31") (name "Net-(U$1-PD0)") (class "Default")
      (node (ref "R11") (pin "2") (pinfunction "2_2") (pintype "passive"))
      (node (ref "U$1") (pin "P81") (pinfunction "PD0_P81") (pintype "bidirectional"))
    )
    (net (code "32") (name "Net-(U$1-PD1)") (class "Default")
      (node (ref "R10") (pin "2") (pinfunction "2_2") (pintype "passive"))
      (node (ref "U$1") (pin "P82") (pinfunction "PD1_P82") (pintype "bidirectional"))
    )
    (net (code "33") (name "Net-(U$1-PD2)") (class "Default")
      (node (ref "R9") (pin "2") (pinfunction "2_2") (pintype "passive"))
      (node (ref "U$1") (pin "P83") (pinfunction "PD2_P83") (pintype "bidirectional"))
    )
    (net (code "34") (name "Net-(U$1-PD3)") (class "Default")
      (node (ref "R8") (pin "2") (pinfunction "2_2") (pintype "passive"))
      (node (ref "U$1") (pin "P84") (pinfunction "PD3_P84") (pintype "bidirectional"))
    )
    (net (code "35") (name "Net-(U$1-PH0)") (class "Default")
      (node (ref "C13") (pin "1") (pinfunction "1_1") (pintype "passive"))
      (node (ref "U$1") (pin "P12") (pinfunction "PH0_P12") (pintype "bidirectional"))
      (node (ref "Y1") (pin "3") (pinfunction "3_3") (pintype "passive"))
    )
    (net (code "36") (name "Net-(U$1-PH1)") (class "Default")
      (node (ref "R3") (pin "1") (pinfunction "1_1") (pintype "passive"))
      (node (ref "U$1") (pin "P13") (pinfunction "PH1_P13") (pintype "bidirectional"))
    )
    (net (code "37") (name "Net-(U$1-VCAP_1)") (class "Default")
      (node (ref "C9") (pin "1") (pinfunction "1_1") (pintype "passive"))
      (node (ref "U$1") (pin "P49") (pinfunction "VCAP_1_P49") (pintype "bidirectional"))
    )
    (net (code "38") (name "Net-(U$1-VCAP_2)") (class "Default")
      (node (ref "C10") (pin "1") (pinfunction "1_1") (pintype "passive"))
      (node (ref "U$1") (pin "P73") (pinfunction "VCAP_2_P73") (pintype "bidirectional"))
    )
    (net (code "39") (name "Net-(U$2-BYPASS)") (class "Default")
      (node (ref "C18") (pin "1") (pinfunction "1_1") (pintype "passive"))
      (node (ref "U$2") (pin "P4") (pinfunction "BYPASS_P4") (pintype "bidirectional"))
    )
    (net (code "40") (name "Net-(U$7-BYPASS)") (class "Default")
      (node (ref "C21") (pin "1") (pinfunction "1_1") (pintype "passive"))
      (node (ref "U$7") (pin "P4") (pinfunction "BYPASS_P4") (pintype "bidirectional"))
    )
    (net (code "41") (name "Net-(U$31-P2)") (class "Default")
      (node (ref "R1") (pin "1") (pinfunction "1_1") (pintype "passive"))
      (node (ref "U$31") (pin "P$2") (pinfunction "P2_P$2") (pintype "bidirectional"))
    )
    (net (code "42") (name "PCLK") (class "Default")
      (node (ref "U$1") (pin "P31") (pinfunction "PA6_P31") (pintype "bidirectional"))
      (node (ref "U$11") (pin "P17") (pinfunction "P17_P17") (pintype "bidirectional"))
    )
    (net (code "43") (name "SWCLK") (class "Default")
      (node (ref "U$1") (pin "P76") (pinfunction "PA14_P76") (pintype "bidirectional"))
      (node (ref "U$63") (pin "P$1") (pinfunction "P$1_P$1") (pintype "bidirectional"))
    )
    (net (code "44") (name "SWDIO") (class "Default")
      (node (ref "U$1") (pin "P72") (pinfunction "PA13_P72") (pintype "bidirectional"))
      (node (ref "U$64") (pin "P$1") (pinfunction "P$1_P$1") (pintype "bidirectional"))
    )
    (net (code "45") (name "UART4_RX") (class "Default")
      (node (ref "U$1") (pin "P24") (pinfunction "PA1_P24") (pintype "bidirectional"))
      (node (ref "U$52") (pin "P11") (pinfunction "P11_P11") (pintype "bidirectional"))
    )
    (net (code "46") (name "UART4_TX") (class "Default")
      (node (ref "U$1") (pin "P23") (pinfunction "PA0_P23") (pintype "bidirectional"))
      (node (ref "U$52") (pin "P10") (pinfunction "P10_P10") (pintype "bidirectional"))
    )
    (net (code "47") (name "USB_D+") (class "Default")
      (node (ref "U$1") (pin "P71") (pinfunction "PA12_P71") (pintype "bidirectional"))
      (node (ref "U$4") (pin "P3") (pinfunction "D+_P3") (pintype "bidirectional"))
    )
    (net (code "48") (name "USB_D-") (class "Default")
      (node (ref "U$1") (pin "P70") (pinfunction "PA11_P70") (pintype "bidirectional"))
      (node (ref "U$4") (pin "P2") (pinfunction "D-_P2") (pintype "bidirectional"))
    )
    (net (code "49") (name "USB_ID") (class "Default")
      (node (ref "U$1") (pin "P69") (pinfunction "PA10_P69") (pintype "bidirectional"))
      (node (ref "U$4") (pin "P4") (pinfunction "ID_P4") (pintype "bidirectional"))
    )
    (net (code "50") (name "USB_VBUS") (class "Default")
      (node (ref "R4") (pin "2") (pinfunction "2_2") (pintype "passive"))
      (node (ref "U$4") (pin "P1") (pinfunction "VCC_P1") (pintype "bidirectional"))
      (node (ref "U$57") (pin "P1") (pinfunction "P1_P1") (pintype "bidirectional"))
    )
    (net (code "51") (name "VBAT") (class "Default")
      (node (ref "C16") (pin "1") (pinfunction "1_1") (pintype "passive"))
      (node (ref "C19") (pin "1") (pinfunction "1_1") (pintype "passive"))
      (node (ref "R12") (pin "2") (pinfunction "2_2") (pintype "passive"))
      (node (ref "R13") (pin "2") (pinfunction "2_2") (pintype "passive"))
      (node (ref "R14") (pin "2") (pinfunction "2_2") (pintype "passive"))
      (node (ref "R15") (pin "2") (pinfunction "2_2") (pintype "passive"))
      (node (ref "U$2") (pin "P1") (pinfunction "IN_P1") (pintype "bidirectional"))
      (node (ref "U$2") (pin "P3") (pinfunction "EN_P3") (pintype "bidirectional"))
      (node (ref "U$5") (pin "P$1") (pinfunction "P$1_P$1") (pintype "bidirectional"))
      (node (ref "U$7") (pin "P1") (pinfunction "IN_P1") (pintype "bidirectional"))
      (node (ref "U$7") (pin "P3") (pinfunction "EN_P3") (pintype "bidirectional"))
    )
    (net (code "52") (name "VBAT_C") (class "Default")
      (node (ref "U$53") (pin "P1") (pinfunction "P1_P1") (pintype "bidirectional"))
      (node (ref "U$55") (pin "P1") (pinfunction "P1_P1") (pintype "bidirectional"))
    )
    (net (code "53") (name "VBAT_P") (class "Default")
      (node (ref "U$54") (pin "P1") (pinfunction "P1_P1") (pintype "bidirectional"))
      (node (ref "U$59") (pin "P1") (pinfunction "P1_P1") (pintype "bidirectional"))
    )
    (net (code "54") (name "VBAT_S") (class "Default")
      (node (ref "U$52") (pin "P1") (pinfunction "P1_P1") (pintype "bidirectional"))
      (node (ref "U$61") (pin "P1") (pinfunction "P1_P1") (pintype "bidirectional"))
    )
    (net (code "55") (name "VCC") (class "Default")
      (node (ref "C1") (pin "1") (pinfunction "1_1") (pintype "passive"))
      (node (ref "C17") (pin "2") (pinfunction "2_2") (pintype "passive"))
      (node (ref "C2") (pin "1") (pinfunction "1_1") (pintype "passive"))
      (node (ref "C22") (pin "1") (pinfunction "1_1") (pintype "passive"))
      (node (ref "C25") (pin "1") (pinfunction "1_1") (pintype "passive"))
      (node (ref "C26") (pin "1") (pinfunction "1_1") (pintype "passive"))
      (node (ref "C3") (pin "1") (pinfunction "1_1") (pintype "passive"))
      (node (ref "C4") (pin "1") (pinfunction "1_1") (pintype "passive"))
      (node (ref "C5") (pin "1") (pinfunction "1_1") (pintype "passive"))
      (node (ref "C6") (pin "1") (pinfunction "1_1") (pintype "passive"))
      (node (ref "C8") (pin "1") (pinfunction "1_1") (pintype "passive"))
      (node (ref "R16") (pin "2") (pinfunction "2_2") (pintype "passive"))
      (node (ref "R18") (pin "2") (pinfunction "2_2") (pintype "passive"))
      (node (ref "U$1") (pin "P100") (pinfunction "VDD6_P100") (pintype "bidirectional"))
      (node (ref "U$1") (pin "P11") (pinfunction "VDD1_P11") (pintype "bidirectional"))
      (node (ref "U$1") (pin "P19") (pinfunction "VDD2_P19") (pintype "bidirectional"))
      (node (ref "U$1") (pin "P28") (pinfunction "VDD3_P28") (pintype "bidirectional"))
      (node (ref "U$1") (pin "P50") (pinfunction "VDD4_P50") (pintype "bidirectional"))
      (node (ref "U$1") (pin "P6") (pinfunction "VBAT_P6") (pintype "bidirectional"))
      (node (ref "U$1") (pin "P75") (pinfunction "VDD5_P75") (pintype "bidirectional"))
      (node (ref "U$11") (pin "P10") (pinfunction "P10_P10") (pintype "bidirectional"))
      (node (ref "U$2") (pin "P5") (pinfunction "OUT_P5") (pintype "bidirectional"))
      (node (ref "U$31") (pin "P$1") (pinfunction "P1_P$1") (pintype "bidirectional"))
      (node (ref "U1") (pin "1") (pinfunction "RESV(VDDIO)_1") (pintype "passive"))
      (node (ref "U1") (pin "10") (pinfunction "REGOUT_10") (pintype "passive"))
      (node (ref "U1") (pin "22") (pinfunction "CSN_22") (pintype "input"))
      (node (ref "U1") (pin "8") (pinfunction "VDDIO_8") (pintype "power_in"))
    )
    (net (code "56") (name "VCC_ANA") (class "Default")
      (node (ref "C20") (pin "2") (pinfunction "2_2") (pintype "passive"))
      (node (ref "C23") (pin "1") (pinfunction "1_1") (pintype "passive"))
      (node (ref "C24") (pin "1") (pinfunction "1_1") (pintype "passive"))
      (node (ref "C7") (pin "1") (pinfunction "1_1") (pintype "passive"))
      (node (ref "U$1") (pin "P21") (pinfunction "VREF+_P21") (pintype "bidirectional"))
      (node (ref "U$1") (pin "P22") (pinfunction "VDDA_P22") (pintype "bidirectional"))
      (node (ref "U$11") (pin "P16") (pinfunction "P16_P16") (pintype "bidirectional"))
      (node (ref "U$7") (pin "P5") (pinfunction "OUT_P5") (pintype "bidirectional"))
      (node (ref "U1") (pin "13") (pinfunction "VDD_13") (pintype "power_in"))
    )
    (net (code "57") (name "VSYNC") (class "Default")
      (node (ref "U$1") (pin "P93") (pinfunction "PB7_P93") (pintype "bidirectional"))
      (node (ref "U$11") (pin "P15") (pinfunction "P15_P15") (pintype "bidirectional"))
    )
    (net (code "58") (name "XCLK") (class "Default")
      (node (ref "U$1") (pin "P67") (pinfunction "PA8_P67") (pintype "bidirectional"))
      (node (ref "U$11") (pin "P18") (pinfunction "P18_P18") (pintype "bidirectional"))
    )
    (net (code "59") (name "unconnected-(U$1-PA2-PadP25)") (class "Default")
      (node (ref "U$1") (pin "P25") (pinfunction "PA2_P25") (pintype "bidirectional"))
    )
    (net (code "60") (name "unconnected-(U$1-PA3-PadP26)") (class "Default")
      (node (ref "U$1") (pin "P26") (pinfunction "PA3_P26") (pintype "bidirectional"))
    )
    (net (code "61") (name "unconnected-(U$1-PA5-PadP30)") (class "Default")
      (node (ref "U$1") (pin "P30") (pinfunction "PA5_P30") (pintype "bidirectional"))
    )
    (net (code "62") (name "unconnected-(U$1-PA7-PadP32)") (class "Default")
      (node (ref "U$1") (pin "P32") (pinfunction "PA7_P32") (pintype "bidirectional"))
    )
    (net (code "63") (name "unconnected-(U$1-PA15-PadP77)") (class "Default")
      (node (ref "U$1") (pin "P77") (pinfunction "PA15_P77") (pintype "bidirectional"))
    )
    (net (code "64") (name "unconnected-(U$1-PB0-PadP35)") (class "Default")
      (node (ref "U$1") (pin "P35") (pinfunction "PB0_P35") (pintype "bidirectional"))
    )
    (net (code "65") (name "unconnected-(U$1-PB1-PadP36)") (class "Default")
      (node (ref "U$1") (pin "P36") (pinfunction "PB1_P36") (pintype "bidirectional"))
    )
    (net (code "66") (name "unconnected-(U$1-PB3-PadP89)") (class "Default")
      (node (ref "U$1") (pin "P89") (pinfunction "PB3_P89") (pintype "bidirectional"))
    )
    (net (code "67") (name "unconnected-(U$1-PB4-PadP90)") (class "Default")
      (node (ref "U$1") (pin "P90") (pinfunction "PB4_P90") (pintype "bidirectional"))
    )
    (net (code "68") (name "unconnected-(U$1-PB5-PadP91)") (class "Default")
      (node (ref "U$1") (pin "P91") (pinfunction "PB5_P91") (pintype "bidirectional"))
    )
    (net (code "69") (name "unconnected-(U$1-PB10-PadP47)") (class "Default")
      (node (ref "U$1") (pin "P47") (pinfunction "PB10_P47") (pintype "bidirectional"))
    )
    (net (code "70") (name "unconnected-(U$1-PB11-PadP48)") (class "Default")
      (node (ref "U$1") (pin "P48") (pinfunction "PB11_P48") (pintype "bidirectional"))
    )
    (net (code "71") (name "unconnected-(U$1-PB14-PadP53)") (class "Default")
      (node (ref "U$1") (pin "P53") (pinfunction "PB14_P53") (pintype "bidirectional"))
    )
    (net (code "72") (name "unconnected-(U$1-PB15-PadP54)") (class "Default")
      (node (ref "U$1") (pin "P54") (pinfunction "PB15_P54") (pintype "bidirectional"))
    )
    (net (code "73") (name "unconnected-(U$1-PC0-PadP15)") (class "Default")
      (node (ref "U$1") (pin "P15") (pinfunction "PC0_P15") (pintype "bidirectional"))
    )
    (net (code "74") (name "unconnected-(U$1-PC1-PadP16)") (class "Default")
      (node (ref "U$1") (pin "P16") (pinfunction "PC1_P16") (pintype "bidirectional"))
    )
    (net (code "75") (name "unconnected-(U$1-PC2-PadP17)") (class "Default")
      (node (ref "U$1") (pin "P17") (pinfunction "PC2_P17") (pintype "bidirectional"))
    )
    (net (code "76") (name "unconnected-(U$1-PC3-PadP18)") (class "Default")
      (node (ref "U$1") (pin "P18") (pinfunction "PC3_P18") (pintype "bidirectional"))
    )
    (net (code "77") (name "unconnected-(U$1-PC4-PadP33)") (class "Default")
      (node (ref "U$1") (pin "P33") (pinfunction "PC4_P33") (pintype "bidirectional"))
    )
    (net (code "78") (name "unconnected-(U$1-PC5-PadP34)") (class "Default")
      (node (ref "U$1") (pin "P34") (pinfunction "PC5_P34") (pintype "bidirectional"))
    )
    (net (code "79") (name "unconnected-(U$1-PC10-PadP78)") (class "Default")
      (node (ref "U$1") (pin "P78") (pinfunction "PC10_P78") (pintype "bidirectional"))
    )
    (net (code "80") (name "unconnected-(U$1-PC12-PadP80)") (class "Default")
      (node (ref "U$1") (pin "P80") (pinfunction "PC12_P80") (pintype "bidirectional"))
    )
    (net (code "81") (name "unconnected-(U$1-PC13-PadP7)") (class "Default")
      (node (ref "U$1") (pin "P7") (pinfunction "PC13_P7") (pintype "bidirectional"))
    )
    (net (code "82") (name "unconnected-(U$1-PC14-PadP8)") (class "Default")
      (node (ref "U$1") (pin "P8") (pinfunction "PC14_P8") (pintype "bidirectional"))
    )
    (net (code "83") (name "unconnected-(U$1-PC15-PadP9)") (class "Default")
      (node (ref "U$1") (pin "P9") (pinfunction "PC15_P9") (pintype "bidirectional"))
    )
    (net (code "84") (name "unconnected-(U$1-PD4-PadP85)") (class "Default")
      (node (ref "U$1") (pin "P85") (pinfunction "PD4_P85") (pintype "bidirectional"))
    )
    (net (code "85") (name "unconnected-(U$1-PD5-PadP86)") (class "Default")
      (node (ref "U$1") (pin "P86") (pinfunction "PD5_P86") (pintype "bidirectional"))
    )
    (net (code "86") (name "unconnected-(U$1-PD6-PadP87)") (class "Default")
      (node (ref "U$1") (pin "P87") (pinfunction "PD6_P87") (pintype "bidirectional"))
    )
    (net (code "87") (name "unconnected-(U$1-PD7-PadP88)") (class "Default")
      (node (ref "U$1") (pin "P88") (pinfunction "PD7_P88") (pintype "bidirectional"))
    )
    (net (code "88") (name "unconnected-(U$1-PD8-PadP55)") (class "Default")
      (node (ref "U$1") (pin "P55") (pinfunction "PD8_P55") (pintype "bidirectional"))
    )
    (net (code "89") (name "unconnected-(U$1-PD9-PadP56)") (class "Default")
      (node (ref "U$1") (pin "P56") (pinfunction "PD9_P56") (pintype "bidirectional"))
    )
    (net (code "90") (name "unconnected-(U$1-PD10-PadP57)") (class "Default")
      (node (ref "U$1") (pin "P57") (pinfunction "PD10_P57") (pintype "bidirectional"))
    )
    (net (code "91") (name "unconnected-(U$1-PD11-PadP58)") (class "Default")
      (node (ref "U$1") (pin "P58") (pinfunction "PD11_P58") (pintype "bidirectional"))
    )
    (net (code "92") (name "unconnected-(U$1-PD12-PadP59)") (class "Default")
      (node (ref "U$1") (pin "P59") (pinfunction "PD12_P59") (pintype "bidirectional"))
    )
    (net (code "93") (name "unconnected-(U$1-PD13-PadP60)") (class "Default")
      (node (ref "U$1") (pin "P60") (pinfunction "PD13_P60") (pintype "bidirectional"))
    )
    (net (code "94") (name "unconnected-(U$1-PD14-PadP61)") (class "Default")
      (node (ref "U$1") (pin "P61") (pinfunction "PD14_P61") (pintype "bidirectional"))
    )
    (net (code "95") (name "unconnected-(U$1-PD15-PadP62)") (class "Default")
      (node (ref "U$1") (pin "P62") (pinfunction "PD15_P62") (pintype "bidirectional"))
    )
    (net (code "96") (name "unconnected-(U$1-PE0-PadP97)") (class "Default")
      (node (ref "U$1") (pin "P97") (pinfunction "PE0_P97") (pintype "bidirectional"))
    )
    (net (code "97") (name "unconnected-(U$1-PE1-PadP98)") (class "Default")
      (node (ref "U$1") (pin "P98") (pinfunction "PE1_P98") (pintype "bidirectional"))
    )
    (net (code "98") (name "unconnected-(U$1-PE2-PadP1)") (class "Default")
      (node (ref "U$1") (pin "P1") (pinfunction "PE2_P1") (pintype "bidirectional"))
    )
    (net (code "99") (name "unconnected-(U$1-PE3-PadP2)") (class "Default")
      (node (ref "U$1") (pin "P2") (pinfunction "PE3_P2") (pintype "bidirectional"))
    )
    (net (code "100") (name "unconnected-(U$1-PE4-PadP3)") (class "Default")
      (node (ref "U$1") (pin "P3") (pinfunction "PE4_P3") (pintype "bidirectional"))
    )
    (net (code "101") (name "unconnected-(U$1-PE7-PadP38)") (class "Default")
      (node (ref "U$1") (pin "P38") (pinfunction "PE7_P38") (pintype "bidirectional"))
    )
    (net (code "102") (name "unconnected-(U$1-PE8-PadP39)") (class "Default")
      (node (ref "U$1") (pin "P39") (pinfunction "PE8_P39") (pintype "bidirectional"))
    )
    (net (code "103") (name "unconnected-(U$1-PE9-PadP40)") (class "Default")
      (node (ref "U$1") (pin "P40") (pinfunction "PE9_P40") (pintype "bidirectional"))
    )
    (net (code "104") (name "unconnected-(U$1-PE10-PadP41)") (class "Default")
      (node (ref "U$1") (pin "P41") (pinfunction "PE10_P41") (pintype "bidirectional"))
    )
    (net (code "105") (name "unconnected-(U$1-PE11-PadP42)") (class "Default")
      (node (ref "U$1") (pin "P42") (pinfunction "PE11_P42") (pintype "bidirectional"))
    )
    (net (code "106") (name "unconnected-(U$1-PE12-PadP43)") (class "Default")
      (node (ref "U$1") (pin "P43") (pinfunction "PE12_P43") (pintype "bidirectional"))
    )
    (net (code "107") (name "unconnected-(U$1-PE13-PadP44)") (class "Default")
      (node (ref "U$1") (pin "P44") (pinfunction "PE13_P44") (pintype "bidirectional"))
    )
    (net (code "108") (name "unconnected-(U$1-PE14-PadP45)") (class "Default")
      (node (ref "U$1") (pin "P45") (pinfunction "PE14_P45") (pintype "bidirectional"))
    )
    (net (code "109") (name "unconnected-(U$1-PE15-PadP46)") (class "Default")
      (node (ref "U$1") (pin "P46") (pinfunction "PE15_P46") (pintype "bidirectional"))
    )
    (net (code "110") (name "unconnected-(U$11-PadP1)") (class "Default")
      (node (ref "U$11") (pin "P1") (pinfunction "P1_P1") (pintype "bidirectional"))
    )
    (net (code "111") (name "unconnected-(U$11-PadP11)") (class "Default")
      (node (ref "U$11") (pin "P11") (pinfunction "P11_P11") (pintype "bidirectional"))
    )
    (net (code "112") (name "unconnected-(U$11-PadP12)") (class "Default")
      (node (ref "U$11") (pin "P12") (pinfunction "P12_P12") (pintype "bidirectional"))
    )
    (net (code "113") (name "unconnected-(U$11-PadP14)") (class "Default")
      (node (ref "U$11") (pin "P14") (pinfunction "P14_P14") (pintype "bidirectional"))
    )
    (net (code "114") (name "unconnected-(U$11-PadP24)") (class "Default")
      (node (ref "U$11") (pin "P24") (pinfunction "P24_P24") (pintype "bidirectional"))
    )
    (net (code "115") (name "unconnected-(U$11-PadP25)") (class "Default")
      (node (ref "U$11") (pin "P25") (pinfunction "P25_P25") (pintype "bidirectional"))
    )
    (net (code "116") (name "unconnected-(U$52-PadP3)") (class "Default")
      (node (ref "U$52") (pin "P3") (pinfunction "P3_P3") (pintype "bidirectional"))
    )
    (net (code "117") (name "unconnected-(U$52-PadP4)") (class "Default")
      (node (ref "U$52") (pin "P4") (pinfunction "P4_P4") (pintype "bidirectional"))
    )
    (net (code "118") (name "unconnected-(U$52-PadP5)") (class "Default")
      (node (ref "U$52") (pin "P5") (pinfunction "P5_P5") (pintype "bidirectional"))
    )
    (net (code "119") (name "unconnected-(U$52-PadP6)") (class "Default")
      (node (ref "U$52") (pin "P6") (pinfunction "P6_P6") (pintype "bidirectional"))
    )
    (net (code "120") (name "unconnected-(U$52-PadP7)") (class "Default")
      (node (ref "U$52") (pin "P7") (pinfunction "P7_P7") (pintype "bidirectional"))
    )
    (net (code "121") (name "unconnected-(U$52-PadP8)") (class "Default")
      (node (ref "U$52") (pin "P8") (pinfunction "P8_P8") (pintype "bidirectional"))
    )
    (net (code "122") (name "unconnected-(U$52-PadP9)") (class "Default")
      (node (ref "U$52") (pin "P9") (pinfunction "P9_P9") (pintype "bidirectional"))
    )
    (net (code "123") (name "unconnected-(U$52-PadP12)") (class "Default")
      (node (ref "U$52") (pin "P12") (pinfunction "P12_P12") (pintype "bidirectional"))
    )
    (net (code "124") (name "unconnected-(U$52-PadP13)") (class "Default")
      (node (ref "U$52") (pin "P13") (pinfunction "P13_P13") (pintype "bidirectional"))
    )
    (net (code "125") (name "unconnected-(U$52-PadP18)") (class "Default")
      (node (ref "U$52") (pin "P18") (pinfunction "P18_P18") (pintype "bidirectional"))
    )
    (net (code "126") (name "unconnected-(U1-AD0{slash}SDO-Pad9)") (class "Default")
      (node (ref "U1") (pin "9") (pinfunction "AD0/SDO_9") (pintype "bidirectional"))
    )
    (net (code "127") (name "unconnected-(U1-AUX_CLK-Pad7)") (class "Default")
      (node (ref "U1") (pin "7") (pinfunction "AUX_CLK_7") (pintype "open_collector"))
    )
    (net (code "128") (name "unconnected-(U1-AUX_DA-Pad21)") (class "Default")
      (node (ref "U1") (pin "21") (pinfunction "AUX_DA_21") (pintype "open_collector"))
    )
    (net (code "129") (name "unconnected-(U1-INT-Pad12)") (class "Default")
      (node (ref "U1") (pin "12") (pinfunction "INT_12") (pintype "open_collector"))
    )
    (net (code "130") (name "unconnected-(U1-NC1-Pad2)") (class "Default")
      (node (ref "U1") (pin "2") (pinfunction "NC1_2") (pintype "passive"))
    )
    (net (code "131") (name "unconnected-(U1-NC2-Pad3)") (class "Default")
      (node (ref "U1") (pin "3") (pinfunction "NC2_3") (pintype "passive"))
    )
    (net (code "132") (name "unconnected-(U1-NC3-Pad4)") (class "Default")
      (node (ref "U1") (pin "4") (pinfunction "NC3_4") (pintype "passive"))
    )
    (net (code "133") (name "unconnected-(U1-NC4-Pad5)") (class "Default")
      (node (ref "U1") (pin "5") (pinfunction "NC4_5") (pintype "passive"))
    )
    (net (code "134") (name "unconnected-(U1-NC5-Pad6)") (class "Default")
      (node (ref "U1") (pin "6") (pinfunction "NC5_6") (pintype "passive"))
    )
    (net (code "135") (name "unconnected-(U1-NC6-Pad14)") (class "Default")
      (node (ref "U1") (pin "14") (pinfunction "NC6_14") (pintype "passive"))
    )
    (net (code "136") (name "unconnected-(U1-NC7-Pad15)") (class "Default")
      (node (ref "U1") (pin "15") (pinfunction "NC7_15") (pintype "passive"))
    )
    (net (code "137") (name "unconnected-(U1-NC8-Pad16)") (class "Default")
      (node (ref "U1") (pin "16") (pinfunction "NC8_16") (pintype "passive"))
    )
    (net (code "138") (name "unconnected-(U1-NC9-Pad17)") (class "Default")
      (node (ref "U1") (pin "17") (pinfunction "NC9_17") (pintype "passive"))
    )
    (net (code "139") (name "unconnected-(U1-RESV-Pad19)") (class "Default")
      (node (ref "U1") (pin "19") (pinfunction "RESV_19") (pintype "passive"))
    )
  )
)
